# WPC-PoweredBoard-AR.net
KiCad netlist of a schematic drawn in EAGLE
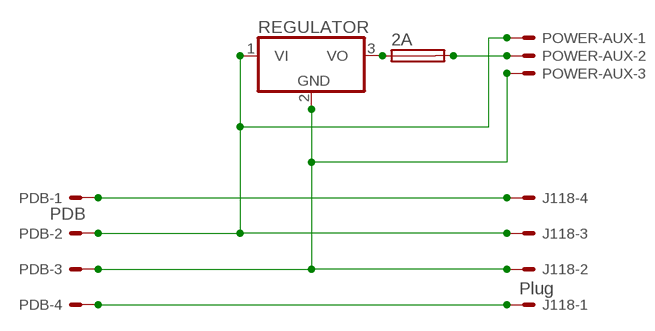
[diagram p0: schematic, sheet 1]

(export (version "E")
  (design (tool "Eeschema 10.0.6"))
  (components
    (comp (ref "2A")
      (value "FUSESHK20L")
      (footprint "eagle-import:SHK20L")
      (libsource (lib "eagle-import") (part "FUSESHK20L"))
    )
    (comp (ref "J118")
      (value "Plug")
      (footprint "eagle-import:KK-156-4")
      (fields (field (name "MF") "MOLEX"))
      (libsource (lib "eagle-import") (part "KK-156-4"))
    )
    (comp (ref "PDB")
      (value "PDB")
      (footprint "eagle-import:KK-156-4")
      (fields (field (name "MF") "MOLEX"))
      (libsource (lib "eagle-import") (part "KK-156-4"))
    )
    (comp (ref "POWER-AUX")
      (value "22-23-2031")
      (footprint "eagle-import:22-23-2031")
      (fields (field (name "MF") "MOLEX"))
      (libsource (lib "eagle-import") (part "22-23-2031"))
    )
    (comp (ref "REGULATOR")
      (value "786TV")
      (footprint "eagle-import:TO220V")
      (libsource (lib "eagle-import") (part "78TV6"))
    )
  )
  (nets
    (net (code "1") (name "Net-(2A-1)") (class "Default")
      (node (ref "2A") (pin "1A") (pinfunction "1_1A") (pintype "passive"))
      (node (ref "REGULATOR") (pin "3") (pinfunction "VO_3") (pintype "passive"))
    )
    (net (code "2") (name "Net-(2A-2)") (class "Default")
      (node (ref "2A") (pin "2A") (pinfunction "2_2A") (pintype "passive"))
      (node (ref "POWER-AUX") (pin "2") (pinfunction "S_2") (pintype "passive"))
    )
    (net (code "3") (name "Net-(J118A-S)") (class "Default")
      (node (ref "J118") (pin "1") (pinfunction "S_1") (pintype "passive"))
      (node (ref "PDB") (pin "4") (pinfunction "S_4") (pintype "passive"))
    )
    (net (code "4") (name "Net-(J118B-S)") (class "Default")
      (node (ref "J118") (pin "2") (pinfunction "S_2") (pintype "passive"))
      (node (ref "PDB") (pin "3") (pinfunction "S_3") (pintype "passive"))
      (node (ref "POWER-AUX") (pin "3") (pinfunction "S_3") (pintype "passive"))
      (node (ref "REGULATOR") (pin "2") (pinfunction "GND_2") (pintype "passive"))
    )
    (net (code "5") (name "Net-(J118C-S)") (class "Default")
      (node (ref "J118") (pin "3") (pinfunction "S_3") (pintype "passive"))
      (node (ref "PDB") (pin "2") (pinfunction "S_2") (pintype "passive"))
      (node (ref "POWER-AUX") (pin "1") (pinfunction "S_1") (pintype "passive"))
      (node (ref "REGULATOR") (pin "1") (pinfunction "VI_1") (pintype "input"))
    )
    (net (code "6") (name "Net-(J118D-S)") (class "Default")
      (node (ref "J118") (pin "4") (pinfunction "S_4") (pintype "passive"))
      (node (ref "PDB") (pin "1") (pinfunction "S_1") (pintype "passive"))
    )
  )
)
